# schema1.net
KiCad netlist of a schematic drawn in EAGLE
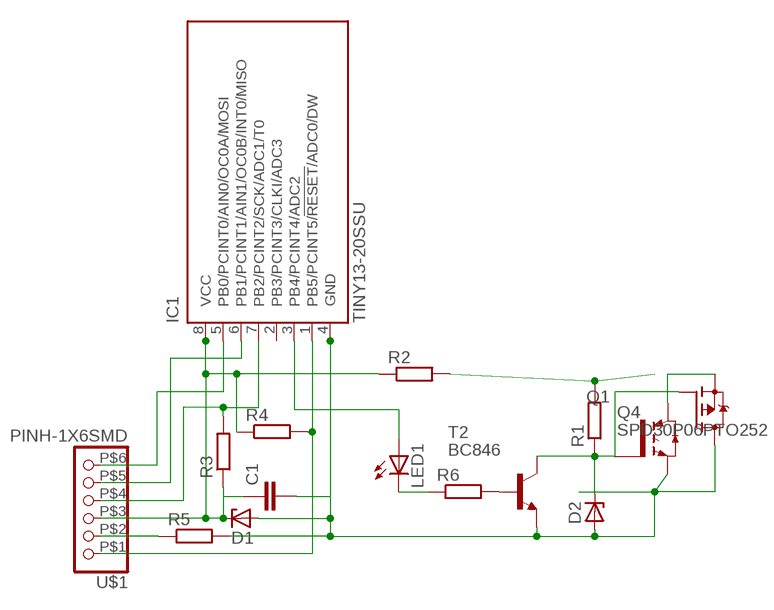
[diagram p0: schematic, sheet 1]

(export (version "E")
  (design (tool "Eeschema 10.0.6"))
  (components
    (comp (ref "C1")
      (value "C-EUC0603")
      (footprint "eagle-import:C0603")
      (libsource (lib "eagle-import") (part "C-EUC0603"))
    )
    (comp (ref "D1")
      (value "ZENER-DIODESOD80C")
      (footprint "eagle-import:SOD80C")
      (libsource (lib "eagle-import") (part "ZENER-DIODESOD80C"))
    )
    (comp (ref "D2")
      (value "ZENER-DIODESOD80C")
      (footprint "eagle-import:SOD80C")
      (libsource (lib "eagle-import") (part "ZENER-DIODESOD80C"))
    )
    (comp (ref "IC1")
      (value "TINY13-20SSU")
      (footprint "eagle-import:8S1")
      (fields (field (name "MPN") "ATTINY13-20SSU"))
      (libsource (lib "eagle-import") (part "TINY13SSU-20"))
    )
    (comp (ref "LED1")
      (value "LEDSML1206")
      (footprint "eagle-import:SML1206")
      (libsource (lib "eagle-import") (part "LEDSML1206"))
    )
    (comp (ref "Q1")
      (value "IRG4BC15UD-S")
      (footprint "eagle-import:D2PACK")
      (libsource (lib "eagle-import") (part "IRG4BC15UD-S"))
    )
    (comp (ref "Q4")
      (value "SPD30P06PTO252")
      (footprint "eagle-import:TO252")
      (libsource (lib "eagle-import") (part "SPD30P06PTO252"))
    )
    (comp (ref "R1")
      (value "R-EU_R1206")
      (footprint "eagle-import:R1206")
      (libsource (lib "eagle-import") (part "R-EU_R1206"))
    )
    (comp (ref "R2")
      (value "R-EU_R1206")
      (footprint "eagle-import:R1206")
      (libsource (lib "eagle-import") (part "R-EU_R1206"))
    )
    (comp (ref "R3")
      (value "R-EU_R1206")
      (footprint "eagle-import:R1206")
      (libsource (lib "eagle-import") (part "R-EU_R1206"))
    )
    (comp (ref "R4")
      (value "R-EU_R1206")
      (footprint "eagle-import:R1206")
      (libsource (lib "eagle-import") (part "R-EU_R1206"))
    )
    (comp (ref "R5")
      (value "R-EU_R1206")
      (footprint "eagle-import:R1206")
      (libsource (lib "eagle-import") (part "R-EU_R1206"))
    )
    (comp (ref "R6")
      (value "R-EU_R1206")
      (footprint "eagle-import:R1206")
      (libsource (lib "eagle-import") (part "R-EU_R1206"))
    )
    (comp (ref "T2")
      (value "BC846")
      (footprint "eagle-import:SOT23")
      (libsource (lib "eagle-import") (part "BC846"))
    )
    (comp (ref "U$1")
      (value "PINH-1X6SMD")
      (footprint "eagle-import:1X06_90SMD")
      (libsource (lib "eagle-import") (part "PINH-1X6SMD"))
    )
  )
  (nets
    (net (code "1") (name "Net-(IC1-GND)") (class "Default")
      (node (ref "C1") (pin "2") (pinfunction "2_2") (pintype "passive"))
      (node (ref "D1") (pin "A") (pinfunction "A_A") (pintype "passive"))
      (node (ref "D2") (pin "A") (pinfunction "A_A") (pintype "passive"))
      (node (ref "IC1") (pin "4") (pinfunction "GND_4") (pintype "power_in"))
      (node (ref "Q1") (pin "3") (pinfunction "E_3") (pintype "passive"))
      (node (ref "Q4") (pin "3") (pinfunction "D_3") (pintype "passive"))
      (node (ref "R5") (pin "2") (pinfunction "2_2") (pintype "passive"))
      (node (ref "T2") (pin "2") (pinfunction "E_2") (pintype "passive"))
    )
    (net (code "2") (name "Net-(IC1-PB0{slash}PCINT0{slash}AIN0{slash}OC0A{slash}MOSI)") (class "Default")
      (node (ref "IC1") (pin "5") (pinfunction "PB0/PCINT0/AIN0/OC0A/MOSI_5") (pintype "bidirectional"))
      (node (ref "U$1") (pin "P$6") (pinfunction "6_P$6") (pintype "passive"))
    )
    (net (code "3") (name "Net-(IC1-PB1{slash}PCINT1{slash}AIN1{slash}OC0B{slash}INT0{slash}MISO)") (class "Default")
      (node (ref "IC1") (pin "6") (pinfunction "PB1/PCINT1/AIN1/OC0B/INT0/MISO_6") (pintype "bidirectional"))
      (node (ref "U$1") (pin "P$5") (pinfunction "5_P$5") (pintype "passive"))
    )
    (net (code "4") (name "Net-(IC1-PB2{slash}PCINT2{slash}SCK{slash}ADC1{slash}T0)") (class "Default")
      (node (ref "IC1") (pin "7") (pinfunction "PB2/PCINT2/SCK/ADC1/T0_7") (pintype "bidirectional"))
      (node (ref "R3") (pin "2") (pinfunction "2_2") (pintype "passive"))
      (node (ref "U$1") (pin "P$4") (pinfunction "4_P$4") (pintype "passive"))
    )
    (net (code "5") (name "Net-(IC1-PB4{slash}PCINT4{slash}ADC2)") (class "Default")
      (node (ref "IC1") (pin "3") (pinfunction "PB4/PCINT4/ADC2_3") (pintype "bidirectional"))
      (node (ref "LED1") (pin "A") (pinfunction "A_A") (pintype "passive"))
    )
    (net (code "6") (name "Net-(IC1-PB5{slash}PCINT5{slash}~{RESET}{slash}ADC0{slash}DW)") (class "Default")
      (node (ref "IC1") (pin "1") (pinfunction "PB5/PCINT5/~{RESET}/ADC0/DW_1") (pintype "bidirectional"))
      (node (ref "R4") (pin "2") (pinfunction "2_2") (pintype "passive"))
      (node (ref "U$1") (pin "P$1") (pinfunction "1_P$1") (pintype "passive"))
    )
    (net (code "7") (name "Net-(IC1-VCC)") (class "Default")
      (node (ref "C1") (pin "1") (pinfunction "1_1") (pintype "passive"))
      (node (ref "D1") (pin "C") (pinfunction "C_C") (pintype "passive"))
      (node (ref "IC1") (pin "8") (pinfunction "VCC_8") (pintype "power_in"))
      (node (ref "R2") (pin "1") (pinfunction "1_1") (pintype "passive"))
      (node (ref "R3") (pin "1") (pinfunction "1_1") (pintype "passive"))
      (node (ref "R4") (pin "1") (pinfunction "1_1") (pintype "passive"))
      (node (ref "U$1") (pin "P$3") (pinfunction "3_P$3") (pintype "passive"))
    )
    (net (code "8") (name "Net-(LED1-PadC)") (class "Default")
      (node (ref "LED1") (pin "C") (pinfunction "C_C") (pintype "passive"))
      (node (ref "R6") (pin "1") (pinfunction "1_1") (pintype "passive"))
    )
    (net (code "9") (name "Net-(Q1-C)") (class "Default")
      (node (ref "Q1") (pin "2") (pinfunction "C_2") (pintype "passive"))
      (node (ref "Q4") (pin "2") (pinfunction "S_2") (pintype "passive"))
    )
    (net (code "10") (name "Net-(Q1-G)") (class "Default")
      (node (ref "D2") (pin "C") (pinfunction "C_C") (pintype "passive"))
      (node (ref "Q1") (pin "1") (pinfunction "G_1") (pintype "passive"))
      (node (ref "Q4") (pin "1") (pinfunction "G_1") (pintype "passive"))
      (node (ref "R1") (pin "1") (pinfunction "1_1") (pintype "passive"))
      (node (ref "T2") (pin "3") (pinfunction "C_3") (pintype "passive"))
    )
    (net (code "11") (name "Net-(R1-Pad2)") (class "Default")
      (node (ref "R1") (pin "2") (pinfunction "2_2") (pintype "passive"))
      (node (ref "R2") (pin "2") (pinfunction "2_2") (pintype "passive"))
    )
    (net (code "12") (name "Net-(T2-B)") (class "Default")
      (node (ref "R6") (pin "2") (pinfunction "2_2") (pintype "passive"))
      (node (ref "T2") (pin "1") (pinfunction "B_1") (pintype "passive"))
    )
    (net (code "13") (name "Net-(U$1-2)") (class "Default")
      (node (ref "R5") (pin "1") (pinfunction "1_1") (pintype "passive"))
      (node (ref "U$1") (pin "P$2") (pinfunction "2_P$2") (pintype "passive"))
    )
    (net (code "14") (name "unconnected-(IC1-PB3{slash}PCINT3{slash}CLKI{slash}ADC3-Pad2)") (class "Default")
      (node (ref "IC1") (pin "2") (pinfunction "PB3/PCINT3/CLKI/ADC3_2") (pintype "bidirectional"))
    )
  )
)
